# Slave_2_relays.net
KiCad netlist of a schematic drawn in Altium Designer
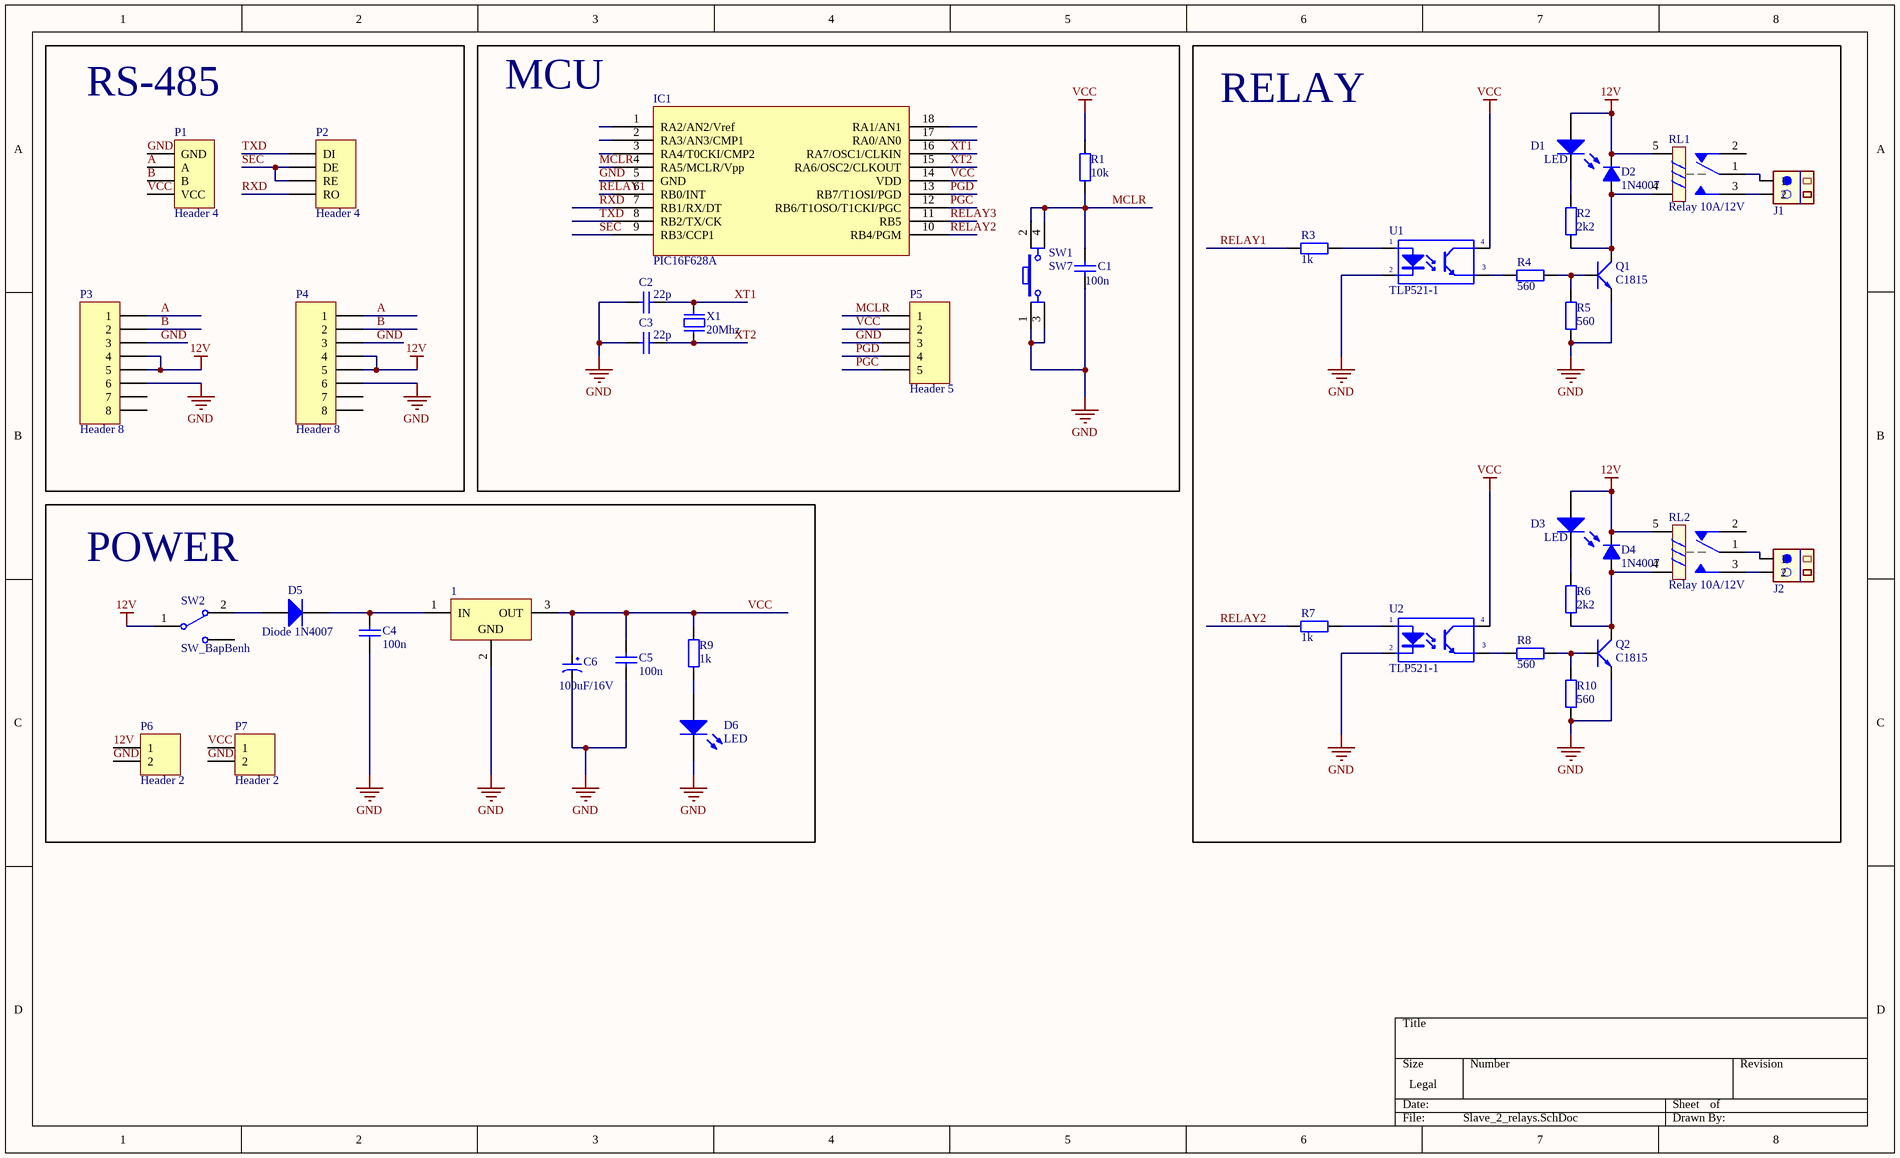
[diagram p0: Slave_2_relays.SchDoc]

(export (version "E")
  (design (tool "Eeschema 10.0.6"))
  (components
    (comp (ref "1")
      (value "L78M05CP")
      (footprint "QTO-220")
      (description "Positive Voltage Regulator")
      (fields (field (name "PUBLISHER") "Altium Limited"))
      (libsource (lib "syhaunguyen") (part "L78M05CP"))
    )
    (comp (ref "C1")
      (value "100n")
      (footprint "Cap Non-Pol 3mm")
      (description "Capacitor")
      (fields (field (name "Comment") "Capacitor Ceramic") (field (name "PUBLISHER") "Altium Limited"))
      (libsource (lib "THG") (part "CapSMD"))
    )
    (comp (ref "C2")
      (value "22p")
      (footprint "Cap Non-Pol 3mm")
      (description "Non-polarized Capacitor")
      (fields (field (name "Comment") "Cap Non-pol") (field (name "PUBLISHER") "Altium Limited"))
      (libsource (lib "THG") (part "Cap Non-pol"))
    )
    (comp (ref "C3")
      (value "22p")
      (footprint "Cap Non-Pol 3mm")
      (description "Non-polarized Capacitor")
      (fields (field (name "Comment") "Cap Non-pol") (field (name "PUBLISHER") "Altium Limited"))
      (libsource (lib "THG") (part "Cap Non-pol"))
    )
    (comp (ref "C4")
      (value "100n")
      (footprint "Cap Non-Pol 3mm")
      (description "Non-polarized Capacitor")
      (fields (field (name "Comment") "Cap Non-pol") (field (name "PUBLISHER") "Altium Limited"))
      (libsource (lib "THG") (part "Cap Non-pol"))
    )
    (comp (ref "C5")
      (value "100n")
      (footprint "Cap Non-Pol 3mm")
      (description "Non-polarized Capacitor")
      (fields (field (name "Comment") "Cap Non-pol") (field (name "PUBLISHER") "Altium Limited"))
      (libsource (lib "THG") (part "Cap Non-pol"))
    )
    (comp (ref "C6")
      (value "100uF/16V")
      (footprint "CP1.5/3.4")
      (description "Cap 100uF/35V - 470uF/16V")
      (libsource (lib "syhaunguyen") (part "CP3"))
    )
    (comp (ref "D1")
      (value "LED")
      (footprint "LED-0 5mm RED")
      (description "Typical LED")
      (fields (field (name "PUBLISHER") "Altium Limited"))
      (libsource (lib "THG") (part "LED"))
    )
    (comp (ref "D2")
      (value "1N4007")
      (footprint "D1A")
      (description "Diode 1A")
      (libsource (lib "syhaunguyen") (part "D1A"))
    )
    (comp (ref "D3")
      (value "LED")
      (footprint "LED-0 5mm RED")
      (description "Typical LED")
      (fields (field (name "PUBLISHER") "Altium Limited"))
      (libsource (lib "THG") (part "LED"))
    )
    (comp (ref "D4")
      (value "1N4007")
      (footprint "D1A")
      (description "Diode 1A")
      (libsource (lib "syhaunguyen") (part "D1A"))
    )
    (comp (ref "D5")
      (value "Diode 1N4007")
      (footprint "DO-41")
      (description "1 Amp General Purpose Rectifier")
      (fields (field (name "PUBLISHER") "Altium Limited"))
      (libsource (lib "hphonglib") (part "Diode 1N4007"))
    )
    (comp (ref "D6")
      (value "LED")
      (footprint "LED-5mm RED")
      (description "Typical LED")
      (fields (field (name "PUBLISHER") "Altium Limited"))
      (libsource (lib "THG") (part "LED"))
    )
    (comp (ref "IC1")
      (value "PIC16F628A")
      (footprint "DIP18/W0.3")
      (libsource (lib "THG") (part "PIC16F628A"))
    )
    (comp (ref "J1")
      (value "CON.Domino2")
      (footprint "DOMINO 2B")
      (description "2 pins Domino Header")
      (fields (field (name "PUBLISHER") "Hoang Nguyen"))
      (libsource (lib "THG") (part "CON.Domino2"))
    )
    (comp (ref "J2")
      (value "CON.Domino2")
      (footprint "DOMINO 2B")
      (description "2 pins Domino Header")
      (fields (field (name "PUBLISHER") "Hoang Nguyen"))
      (libsource (lib "THG") (part "CON.Domino2"))
    )
    (comp (ref "P1")
      (value "Header 4")
      (footprint "HDR1X4")
      (description "Header, 4-Pin")
      (fields (field (name "PUBLISHER") "Altium Limited"))
      (libsource (lib "Miscellaneous Connectors") (part "Header 4"))
    )
    (comp (ref "P2")
      (value "Header 4")
      (footprint "HDR1X4")
      (description "Header, 4-Pin")
      (fields (field (name "PUBLISHER") "Altium Limited"))
      (libsource (lib "Miscellaneous Connectors") (part "Header 4"))
    )
    (comp (ref "P3")
      (value "Header 8")
      (footprint "RJ11")
      (description "Header, 8-Pin")
      (fields (field (name "PUBLISHER") "Altium Limited"))
      (libsource (lib "THG") (part "Header 8"))
    )
    (comp (ref "P4")
      (value "Header 8")
      (footprint "RJ11")
      (description "Header, 8-Pin")
      (fields (field (name "PUBLISHER") "Altium Limited"))
      (libsource (lib "THG") (part "Header 8"))
    )
    (comp (ref "P5")
      (value "Header 5")
      (footprint "Header 5")
      (description "Header, 5-Pin")
      (fields (field (name "PUBLISHER") "Altium Limited"))
      (libsource (lib "THG") (part "Header 5"))
    )
    (comp (ref "P6")
      (value "Header 2")
      (footprint "HDR1X2")
      (description "Header, 2-Pin")
      (fields (field (name "PUBLISHER") "Altium Limited"))
      (libsource (lib "Miscellaneous Connectors") (part "Header 2"))
    )
    (comp (ref "P7")
      (value "Header 2")
      (footprint "HDR1X2")
      (description "Header, 2-Pin")
      (fields (field (name "PUBLISHER") "Altium Limited"))
      (libsource (lib "Miscellaneous Connectors") (part "Header 2"))
    )
    (comp (ref "Q1")
      (value "C1815")
      (footprint "QTO-92")
      (description "NPN 600mW, ECB")
      (libsource (lib "syhaunguyen") (part "C1815"))
    )
    (comp (ref "Q2")
      (value "C1815")
      (footprint "QTO-92")
      (description "NPN 600mW, ECB")
      (libsource (lib "syhaunguyen") (part "C1815"))
    )
    (comp (ref "R1")
      (value "10k")
      (footprint "RESISTOR 1/4W")
      (description "RES_0805")
      (fields (field (name "Comment") "RES_SMD_0805") (field (name "PUBLISHER") "Altium Limited"))
      (libsource (lib "") (part "RES_SMD_0805_1"))
    )
    (comp (ref "R2")
      (value "2k2")
      (footprint "RESISTOR 1/4W")
      (description "RES_0805")
      (fields (field (name "Comment") "RES_SMD_0805") (field (name "PUBLISHER") "Altium Limited"))
      (libsource (lib "THG") (part "RES_SMD_0805"))
    )
    (comp (ref "R3")
      (value "1k")
      (footprint "RESISTOR 1/4W")
      (description "RES_0805")
      (fields (field (name "Comment") "RES_SMD_0805") (field (name "PUBLISHER") "Altium Limited"))
      (libsource (lib "") (part "RES_SMD_0805_2"))
    )
    (comp (ref "R4")
      (value "560")
      (footprint "RESISTOR 1/4W")
      (description "RES_0805")
      (fields (field (name "Comment") "RES_SMD_0805") (field (name "PUBLISHER") "Altium Limited"))
      (libsource (lib "") (part "RES_SMD_0805_2"))
    )
    (comp (ref "R5")
      (value "560")
      (footprint "RESISTOR 1/4W")
      (description "RES_0805")
      (fields (field (name "Comment") "RES_SMD_0805") (field (name "PUBLISHER") "Altium Limited"))
      (libsource (lib "THG") (part "RES_SMD_0805"))
    )
    (comp (ref "R6")
      (value "2k2")
      (footprint "RESISTOR 1/4W")
      (description "RES_0805")
      (fields (field (name "Comment") "RES_SMD_0805") (field (name "PUBLISHER") "Altium Limited"))
      (libsource (lib "THG") (part "RES_SMD_0805"))
    )
    (comp (ref "R7")
      (value "1k")
      (footprint "RESISTOR 1/4W")
      (description "RES_0805")
      (fields (field (name "Comment") "RES_SMD_0805") (field (name "PUBLISHER") "Altium Limited"))
      (libsource (lib "") (part "RES_SMD_0805_2"))
    )
    (comp (ref "R8")
      (value "560")
      (footprint "RESISTOR 1/4W")
      (description "RES_0805")
      (fields (field (name "Comment") "RES_SMD_0805") (field (name "PUBLISHER") "Altium Limited"))
      (libsource (lib "") (part "RES_SMD_0805_2"))
    )
    (comp (ref "R9")
      (value "1k")
      (footprint "RESISTOR 1/4W")
      (description "RES_0805")
      (fields (field (name "Comment") "RES_SMD_0805") (field (name "PUBLISHER") "Altium Limited"))
      (libsource (lib "") (part "RES_SMD_0805_1"))
    )
    (comp (ref "R10")
      (value "560")
      (footprint "RESISTOR 1/4W")
      (description "RES_0805")
      (fields (field (name "Comment") "RES_SMD_0805") (field (name "PUBLISHER") "Altium Limited"))
      (libsource (lib "THG") (part "RES_SMD_0805"))
    )
    (comp (ref "RL1")
      (value "Relay 10A/12V")
      (footprint "RL_SPDT_10A")
      (description "Relay SPDT,10A - 12VDC 5 Pin")
      (libsource (lib "syhaunguyen") (part "Relay 1"))
    )
    (comp (ref "RL2")
      (value "Relay 10A/12V")
      (footprint "RL_SPDT_10A")
      (description "Relay SPDT,10A - 12VDC 5 Pin")
      (libsource (lib "syhaunguyen") (part "Relay 1"))
    )
    (comp (ref "SW1")
      (value "SW7")
      (footprint "SW4")
      (description "Switch button 4 pin")
      (libsource (lib "syhaunguyen") (part "SW4"))
    )
    (comp (ref "SW2")
      (value "SW_BapBenh")
      (footprint "SW_Bapbenh")
      (libsource (lib "THG") (part "SW_BapBenh"))
    )
    (comp (ref "U1")
      (value "TLP521-1")
      (footprint "DIP4/W0.3")
      (description "Single Opto")
      (libsource (lib "syhaunguyen") (part "TLP521-1"))
    )
    (comp (ref "U2")
      (value "TLP521-1")
      (footprint "DIP4/W0.3")
      (description "Single Opto")
      (libsource (lib "syhaunguyen") (part "TLP521-1"))
    )
    (comp (ref "X1")
      (value "20Mhz")
      (footprint "XT2")
      (description "Crystal For all Crystal 2pin.")
      (libsource (lib "syhaunguyen") (part "XT2"))
    )
  )
  (nets
    (net (code "1") (name "/A") (class "Default")
      (node (ref "P1") (pin "2") (pinfunction "A_2") (pintype "passive"))
      (node (ref "P3") (pin "1") (pinfunction "1_1") (pintype "passive"))
      (node (ref "P4") (pin "1") (pinfunction "1_1") (pintype "passive"))
    )
    (net (code "2") (name "/B") (class "Default")
      (node (ref "P1") (pin "3") (pinfunction "B_3") (pintype "passive"))
      (node (ref "P3") (pin "2") (pinfunction "2_2") (pintype "passive"))
      (node (ref "P4") (pin "2") (pinfunction "2_2") (pintype "passive"))
    )
    (net (code "3") (name "/MCLR") (class "Default")
      (node (ref "C1") (pin "2") (pinfunction "2_2") (pintype "passive"))
      (node (ref "IC1") (pin "4") (pinfunction "RA5/MCLR/Vpp_4") (pintype "passive"))
      (node (ref "P5") (pin "1") (pinfunction "1_1") (pintype "passive"))
      (node (ref "R1") (pin "1") (pinfunction "1_1") (pintype "passive"))
      (node (ref "SW1") (pin "2") (pintype "passive"))
      (node (ref "SW1") (pin "4") (pintype "passive"))
    )
    (net (code "4") (name "/PGC") (class "Default")
      (node (ref "IC1") (pin "12") (pinfunction "RB6/T1OSO/T1CKI/PGC_12") (pintype "passive"))
      (node (ref "P5") (pin "5") (pinfunction "5_5") (pintype "passive"))
    )
    (net (code "5") (name "/PGD") (class "Default")
      (node (ref "IC1") (pin "13") (pinfunction "RB7/T1OSI/PGD_13") (pintype "passive"))
      (node (ref "P5") (pin "4") (pinfunction "4_4") (pintype "passive"))
    )
    (net (code "6") (name "/RELAY1") (class "Default")
      (node (ref "IC1") (pin "6") (pinfunction "RB0/INT_6") (pintype "passive"))
      (node (ref "R3") (pin "2") (pinfunction "2_2") (pintype "passive"))
    )
    (net (code "7") (name "/RELAY2") (class "Default")
      (node (ref "IC1") (pin "10") (pinfunction "RB4/PGM_10") (pintype "passive"))
      (node (ref "R7") (pin "2") (pinfunction "2_2") (pintype "passive"))
    )
    (net (code "8") (name "/RELAY3") (class "Default")
      (node (ref "IC1") (pin "11") (pinfunction "RB5_11") (pintype "passive"))
    )
    (net (code "9") (name "/RXD") (class "Default")
      (node (ref "IC1") (pin "7") (pinfunction "RB1/RX/DT_7") (pintype "passive"))
      (node (ref "P2") (pin "4") (pinfunction "VCC_4") (pintype "passive"))
    )
    (net (code "10") (name "/SEC") (class "Default")
      (node (ref "IC1") (pin "9") (pinfunction "RB3/CCP1_9") (pintype "passive"))
      (node (ref "P2") (pin "2") (pinfunction "A_2") (pintype "passive"))
      (node (ref "P2") (pin "3") (pinfunction "B_3") (pintype "passive"))
    )
    (net (code "11") (name "/TXD") (class "Default")
      (node (ref "IC1") (pin "8") (pinfunction "RB2/TX/CK_8") (pintype "passive"))
      (node (ref "P2") (pin "1") (pinfunction "GND_1") (pintype "passive"))
    )
    (net (code "12") (name "/XT1") (class "Default")
      (node (ref "C2") (pin "1") (pinfunction "1_1") (pintype "passive"))
      (node (ref "IC1") (pin "16") (pinfunction "RA7/OSC1/CLKIN_16") (pintype "passive"))
      (node (ref "X1") (pin "2") (pinfunction "2_2") (pintype "passive"))
    )
    (net (code "13") (name "/XT2") (class "Default")
      (node (ref "C3") (pin "1") (pinfunction "1_1") (pintype "passive"))
      (node (ref "IC1") (pin "15") (pinfunction "RA6/OSC2/CLKOUT_15") (pintype "passive"))
      (node (ref "X1") (pin "1") (pinfunction "1_1") (pintype "passive"))
    )
    (net (code "14") (name "12V") (class "Default")
      (node (ref "D1") (pin "1") (pinfunction "A_1") (pintype "passive"))
      (node (ref "D2") (pin "2") (pinfunction "K_2") (pintype "passive"))
      (node (ref "D3") (pin "1") (pinfunction "A_1") (pintype "passive"))
      (node (ref "D4") (pin "2") (pinfunction "K_2") (pintype "passive"))
      (node (ref "P3") (pin "4") (pinfunction "4_4") (pintype "passive"))
      (node (ref "P3") (pin "5") (pinfunction "5_5") (pintype "passive"))
      (node (ref "P4") (pin "4") (pinfunction "4_4") (pintype "passive"))
      (node (ref "P4") (pin "5") (pinfunction "5_5") (pintype "passive"))
      (node (ref "P6") (pin "1") (pinfunction "1_1") (pintype "passive"))
      (node (ref "RL1") (pin "5") (pinfunction "5_5") (pintype "passive"))
      (node (ref "RL2") (pin "5") (pinfunction "5_5") (pintype "passive"))
      (node (ref "SW2") (pin "1") (pinfunction "1_1") (pintype "passive"))
    )
    (net (code "15") (name "GND") (class "Default")
      (node (ref "1") (pin "2") (pinfunction "GND_2") (pintype "power_in"))
      (node (ref "C1") (pin "1") (pinfunction "1_1") (pintype "passive"))
      (node (ref "C2") (pin "2") (pinfunction "2_2") (pintype "passive"))
      (node (ref "C3") (pin "2") (pinfunction "2_2") (pintype "passive"))
      (node (ref "C4") (pin "1") (pinfunction "1_1") (pintype "passive"))
      (node (ref "C5") (pin "1") (pinfunction "1_1") (pintype "passive"))
      (node (ref "C6") (pin "2") (pinfunction "2_2") (pintype "passive"))
      (node (ref "D6") (pin "2") (pinfunction "K_2") (pintype "passive"))
      (node (ref "IC1") (pin "5") (pinfunction "GND_5") (pintype "passive"))
      (node (ref "P1") (pin "1") (pinfunction "GND_1") (pintype "passive"))
      (node (ref "P3") (pin "3") (pinfunction "3_3") (pintype "passive"))
      (node (ref "P3") (pin "6") (pinfunction "6_6") (pintype "passive"))
      (node (ref "P4") (pin "3") (pinfunction "3_3") (pintype "passive"))
      (node (ref "P4") (pin "6") (pinfunction "6_6") (pintype "passive"))
      (node (ref "P5") (pin "3") (pinfunction "3_3") (pintype "passive"))
      (node (ref "P6") (pin "2") (pinfunction "2_2") (pintype "passive"))
      (node (ref "P7") (pin "2") (pinfunction "2_2") (pintype "passive"))
      (node (ref "Q1") (pin "1") (pinfunction "E_1") (pintype "passive"))
      (node (ref "Q2") (pin "1") (pinfunction "E_1") (pintype "passive"))
      (node (ref "R10") (pin "2") (pinfunction "2_2") (pintype "passive"))
      (node (ref "R5") (pin "2") (pinfunction "2_2") (pintype "passive"))
      (node (ref "SW1") (pin "1") (pintype "passive"))
      (node (ref "SW1") (pin "3") (pintype "passive"))
      (node (ref "U1") (pin "2") (pinfunction "K_2") (pintype "passive"))
      (node (ref "U2") (pin "2") (pinfunction "K_2") (pintype "passive"))
    )
    (net (code "16") (name "Net-(1-IN)") (class "Default")
      (node (ref "1") (pin "1") (pinfunction "IN_1") (pintype "power_in"))
      (node (ref "C4") (pin "2") (pinfunction "2_2") (pintype "passive"))
      (node (ref "D5") (pin "2") (pinfunction "K_2") (pintype "passive"))
    )
    (net (code "17") (name "Net-(D1-K)") (class "Default")
      (node (ref "D1") (pin "2") (pinfunction "K_2") (pintype "passive"))
      (node (ref "R2") (pin "1") (pinfunction "1_1") (pintype "passive"))
    )
    (net (code "18") (name "Net-(D2-A)") (class "Default")
      (node (ref "D2") (pin "1") (pinfunction "A_1") (pintype "passive"))
      (node (ref "Q1") (pin "2") (pinfunction "C_2") (pintype "passive"))
      (node (ref "R2") (pin "2") (pinfunction "2_2") (pintype "passive"))
      (node (ref "RL1") (pin "4") (pinfunction "4_4") (pintype "passive"))
    )
    (net (code "19") (name "Net-(D3-K)") (class "Default")
      (node (ref "D3") (pin "2") (pinfunction "K_2") (pintype "passive"))
      (node (ref "R6") (pin "1") (pinfunction "1_1") (pintype "passive"))
    )
    (net (code "20") (name "Net-(D4-A)") (class "Default")
      (node (ref "D4") (pin "1") (pinfunction "A_1") (pintype "passive"))
      (node (ref "Q2") (pin "2") (pinfunction "C_2") (pintype "passive"))
      (node (ref "R6") (pin "2") (pinfunction "2_2") (pintype "passive"))
      (node (ref "RL2") (pin "4") (pinfunction "4_4") (pintype "passive"))
    )
    (net (code "21") (name "Net-(D5-A)") (class "Default")
      (node (ref "D5") (pin "1") (pinfunction "A_1") (pintype "passive"))
      (node (ref "SW2") (pin "2") (pinfunction "2_2") (pintype "passive"))
    )
    (net (code "22") (name "Net-(D6-A)") (class "Default")
      (node (ref "D6") (pin "1") (pinfunction "A_1") (pintype "passive"))
      (node (ref "R9") (pin "1") (pinfunction "1_1") (pintype "passive"))
    )
    (net (code "23") (name "Net-(J1-Pad1)") (class "Default")
      (node (ref "J1") (pin "1") (pinfunction "1_1") (pintype "passive"))
      (node (ref "RL1") (pin "1") (pinfunction "1_1") (pintype "passive"))
    )
    (net (code "24") (name "Net-(J1-Pad2)") (class "Default")
      (node (ref "J1") (pin "2") (pinfunction "2_2") (pintype "passive"))
      (node (ref "RL1") (pin "3") (pinfunction "3_3") (pintype "passive"))
    )
    (net (code "25") (name "Net-(J2-Pad1)") (class "Default")
      (node (ref "J2") (pin "1") (pinfunction "1_1") (pintype "passive"))
      (node (ref "RL2") (pin "1") (pinfunction "1_1") (pintype "passive"))
    )
    (net (code "26") (name "Net-(J2-Pad2)") (class "Default")
      (node (ref "J2") (pin "2") (pinfunction "2_2") (pintype "passive"))
      (node (ref "RL2") (pin "3") (pinfunction "3_3") (pintype "passive"))
    )
    (net (code "27") (name "Net-(Q1-B)") (class "Default")
      (node (ref "Q1") (pin "3") (pinfunction "B_3") (pintype "passive"))
      (node (ref "R4") (pin "1") (pinfunction "1_1") (pintype "passive"))
      (node (ref "R5") (pin "1") (pinfunction "1_1") (pintype "passive"))
    )
    (net (code "28") (name "Net-(Q2-B)") (class "Default")
      (node (ref "Q2") (pin "3") (pinfunction "B_3") (pintype "passive"))
      (node (ref "R10") (pin "1") (pinfunction "1_1") (pintype "passive"))
      (node (ref "R8") (pin "1") (pinfunction "1_1") (pintype "passive"))
    )
    (net (code "29") (name "Net-(U1-A)") (class "Default")
      (node (ref "R3") (pin "1") (pinfunction "1_1") (pintype "passive"))
      (node (ref "U1") (pin "1") (pinfunction "A_1") (pintype "passive"))
    )
    (net (code "30") (name "Net-(U1-E)") (class "Default")
      (node (ref "R4") (pin "2") (pinfunction "2_2") (pintype "passive"))
      (node (ref "U1") (pin "3") (pinfunction "E_3") (pintype "passive"))
    )
    (net (code "31") (name "Net-(U2-A)") (class "Default")
      (node (ref "R7") (pin "1") (pinfunction "1_1") (pintype "passive"))
      (node (ref "U2") (pin "1") (pinfunction "A_1") (pintype "passive"))
    )
    (net (code "32") (name "Net-(U2-E)") (class "Default")
      (node (ref "R8") (pin "2") (pinfunction "2_2") (pintype "passive"))
      (node (ref "U2") (pin "3") (pinfunction "E_3") (pintype "passive"))
    )
    (net (code "33") (name "VCC") (class "Default")
      (node (ref "1") (pin "3") (pinfunction "OUT_3") (pintype "power_in"))
      (node (ref "C5") (pin "2") (pinfunction "2_2") (pintype "passive"))
      (node (ref "C6") (pin "1") (pinfunction "1_1") (pintype "passive"))
      (node (ref "IC1") (pin "14") (pinfunction "VDD_14") (pintype "passive"))
      (node (ref "P1") (pin "4") (pinfunction "VCC_4") (pintype "passive"))
      (node (ref "P5") (pin "2") (pinfunction "2_2") (pintype "passive"))
      (node (ref "P7") (pin "1") (pinfunction "1_1") (pintype "passive"))
      (node (ref "R1") (pin "2") (pinfunction "2_2") (pintype "passive"))
      (node (ref "R9") (pin "2") (pinfunction "2_2") (pintype "passive"))
      (node (ref "U1") (pin "4") (pinfunction "C_4") (pintype "passive"))
      (node (ref "U2") (pin "4") (pinfunction "C_4") (pintype "passive"))
    )
    (net (code "34") (name "unconnected-(IC1-RA0{slash}AN0-Pad17)") (class "Default")
      (node (ref "IC1") (pin "17") (pinfunction "RA0/AN0_17") (pintype "passive"))
    )
    (net (code "35") (name "unconnected-(IC1-RA1{slash}AN1-Pad18)") (class "Default")
      (node (ref "IC1") (pin "18") (pinfunction "RA1/AN1_18") (pintype "passive"))
    )
    (net (code "36") (name "unconnected-(IC1-RA2{slash}AN2{slash}Vref-Pad1)") (class "Default")
      (node (ref "IC1") (pin "1") (pinfunction "RA2/AN2/Vref_1") (pintype "passive"))
    )
    (net (code "37") (name "unconnected-(IC1-RA3{slash}AN3{slash}CMP1-Pad2)") (class "Default")
      (node (ref "IC1") (pin "2") (pinfunction "RA3/AN3/CMP1_2") (pintype "passive"))
    )
    (net (code "38") (name "unconnected-(IC1-RA4{slash}T0CKI{slash}CMP2-Pad3)") (class "Default")
      (node (ref "IC1") (pin "3") (pinfunction "RA4/T0CKI/CMP2_3") (pintype "passive"))
    )
    (net (code "39") (name "unconnected-(P3-Pad7)") (class "Default")
      (node (ref "P3") (pin "7") (pinfunction "7_7") (pintype "passive"))
    )
    (net (code "40") (name "unconnected-(P3-Pad8)") (class "Default")
      (node (ref "P3") (pin "8") (pinfunction "8_8") (pintype "passive"))
    )
    (net (code "41") (name "unconnected-(P4-Pad7)") (class "Default")
      (node (ref "P4") (pin "7") (pinfunction "7_7") (pintype "passive"))
    )
    (net (code "42") (name "unconnected-(P4-Pad8)") (class "Default")
      (node (ref "P4") (pin "8") (pinfunction "8_8") (pintype "passive"))
    )
    (net (code "43") (name "unconnected-(RL1-Pad2)") (class "Default")
      (node (ref "RL1") (pin "2") (pinfunction "2_2") (pintype "passive"))
    )
    (net (code "44") (name "unconnected-(RL2-Pad2)") (class "Default")
      (node (ref "RL2") (pin "2") (pinfunction "2_2") (pintype "passive"))
    )
  )
)
